# PCB_Project.net
KiCad netlist of a schematic drawn in Altium Designer
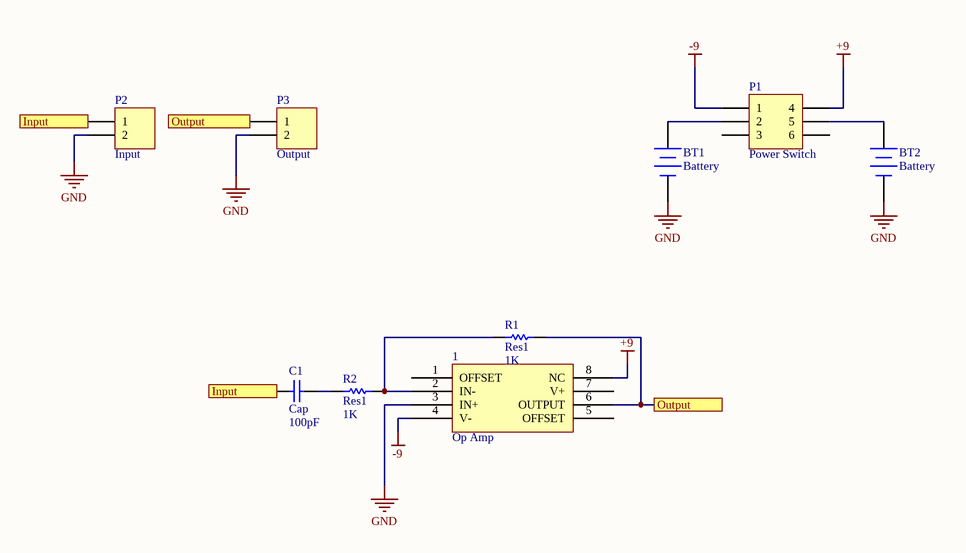
[diagram p0: PCB_Project.SchDoc]

(export (version "E")
  (design (tool "Eeschema 10.0.6"))
  (components
    (comp (ref "1")
      (value "Op Amp")
      (footprint "Op Amp")
      (libsource (lib "PCB_Project") (part "Component_1"))
    )
    (comp (ref "BT1")
      (value "Battery")
      (footprint "BAT-2")
      (description "Multicell Battery")
      (fields (field (name "PUBLISHER") "Altium Limited"))
      (libsource (lib "Miscellaneous Devices") (part "Battery"))
    )
    (comp (ref "BT2")
      (value "Battery")
      (footprint "BAT-2")
      (description "Multicell Battery")
      (fields (field (name "PUBLISHER") "Altium Limited"))
      (libsource (lib "Miscellaneous Devices") (part "Battery"))
    )
    (comp (ref "C1")
      (value "Cap")
      (footprint "RAD-0.3")
      (description "Capacitor")
      (fields (field (name "ALTIUM_VALUE") "100pF") (field (name "PUBLISHER") "Altium Limited"))
      (libsource (lib "Miscellaneous Devices") (part "Cap"))
    )
    (comp (ref "P1")
      (value "Power Switch")
      (footprint "HDR2X3_CEN")
      (description "Header, 3-Pin, Dual row")
      (fields (field (name "PUBLISHER") "Altium Limited"))
      (libsource (lib "Miscellaneous Connectors") (part "Header 3X2A"))
    )
    (comp (ref "P2")
      (value "Input")
      (footprint "MHDR1X2")
      (description "Header, 2-Pin")
      (fields (field (name "PUBLISHER") "Altium Limited"))
      (libsource (lib "Miscellaneous Connectors") (part "MHDR1X2"))
    )
    (comp (ref "P3")
      (value "Output")
      (footprint "MHDR1X2")
      (description "Header, 2-Pin")
      (fields (field (name "PUBLISHER") "Altium Limited"))
      (libsource (lib "Miscellaneous Connectors") (part "MHDR1X2"))
    )
    (comp (ref "R1")
      (value "Res1")
      (footprint "AXIAL-0.3")
      (description "Resistor")
      (fields (field (name "ALTIUM_VALUE") "1K") (field (name "PUBLISHER") "Altium Limited"))
      (libsource (lib "Miscellaneous Devices") (part "Res1"))
    )
    (comp (ref "R2")
      (value "Res1")
      (footprint "AXIAL-0.3")
      (description "Resistor")
      (fields (field (name "ALTIUM_VALUE") "1K") (field (name "PUBLISHER") "Altium Limited"))
      (libsource (lib "Miscellaneous Devices") (part "Res1"))
    )
  )
  (nets
    (net (code "1") (name "+9") (class "Default")
      (node (ref "1") (pin "8") (pinfunction "NC_8") (pintype "passive"))
      (node (ref "P1") (pin "4") (pinfunction "4_4") (pintype "passive"))
    )
    (net (code "2") (name "-9") (class "Default")
      (node (ref "1") (pin "4") (pinfunction "V-_4") (pintype "passive"))
      (node (ref "P1") (pin "1") (pinfunction "1_1") (pintype "passive"))
    )
    (net (code "3") (name "/Input") (class "Default")
      (node (ref "C1") (pin "1") (pinfunction "1_1") (pintype "passive"))
      (node (ref "P2") (pin "1") (pinfunction "1_1") (pintype "passive"))
    )
    (net (code "4") (name "/Output") (class "Default")
      (node (ref "1") (pin "6") (pinfunction "OUTPUT_6") (pintype "passive"))
      (node (ref "P3") (pin "1") (pinfunction "1_1") (pintype "passive"))
      (node (ref "R1") (pin "2") (pinfunction "2_2") (pintype "passive"))
    )
    (net (code "5") (name "GND") (class "Default")
      (node (ref "1") (pin "3") (pinfunction "IN+_3") (pintype "passive"))
      (node (ref "BT1") (pin "2") (pinfunction "-_2") (pintype "passive"))
      (node (ref "BT2") (pin "2") (pinfunction "-_2") (pintype "passive"))
      (node (ref "P2") (pin "2") (pinfunction "2_2") (pintype "passive"))
      (node (ref "P3") (pin "2") (pinfunction "2_2") (pintype "passive"))
    )
    (net (code "6") (name "Net-(1-IN-)") (class "Default")
      (node (ref "1") (pin "2") (pinfunction "IN-_2") (pintype "passive"))
      (node (ref "R1") (pin "1") (pinfunction "1_1") (pintype "passive"))
      (node (ref "R2") (pin "2") (pinfunction "2_2") (pintype "passive"))
    )
    (net (code "7") (name "Net-(BT1-+)") (class "Default")
      (node (ref "BT1") (pin "1") (pinfunction "+_1") (pintype "passive"))
      (node (ref "P1") (pin "2") (pinfunction "2_2") (pintype "passive"))
    )
    (net (code "8") (name "Net-(BT2-+)") (class "Default")
      (node (ref "BT2") (pin "1") (pinfunction "+_1") (pintype "passive"))
      (node (ref "P1") (pin "5") (pinfunction "5_5") (pintype "passive"))
    )
    (net (code "9") (name "Net-(C1-Pad2)") (class "Default")
      (node (ref "C1") (pin "2") (pinfunction "2_2") (pintype "passive"))
      (node (ref "R2") (pin "1") (pinfunction "1_1") (pintype "passive"))
    )
    (net (code "10") (name "unconnected-(1-OFFSET-Pad1)") (class "Default")
      (node (ref "1") (pin "1") (pinfunction "OFFSET_1") (pintype "passive"))
    )
    (net (code "11") (name "unconnected-(1-OFFSET-Pad5)") (class "Default")
      (node (ref "1") (pin "5") (pinfunction "OFFSET_5") (pintype "passive"))
    )
    (net (code "12") (name "unconnected-(1-V+-Pad7)") (class "Default")
      (node (ref "1") (pin "7") (pinfunction "V+_7") (pintype "passive"))
    )
    (net (code "13") (name "unconnected-(P1-Pad3)") (class "Default")
      (node (ref "P1") (pin "3") (pinfunction "3_3") (pintype "passive"))
    )
    (net (code "14") (name "unconnected-(P1-Pad6)") (class "Default")
      (node (ref "P1") (pin "6") (pinfunction "6_6") (pintype "passive"))
    )
  )
)
